# io-16x-fused-fm_beta.net
KiCad netlist of a schematic drawn in EAGLE
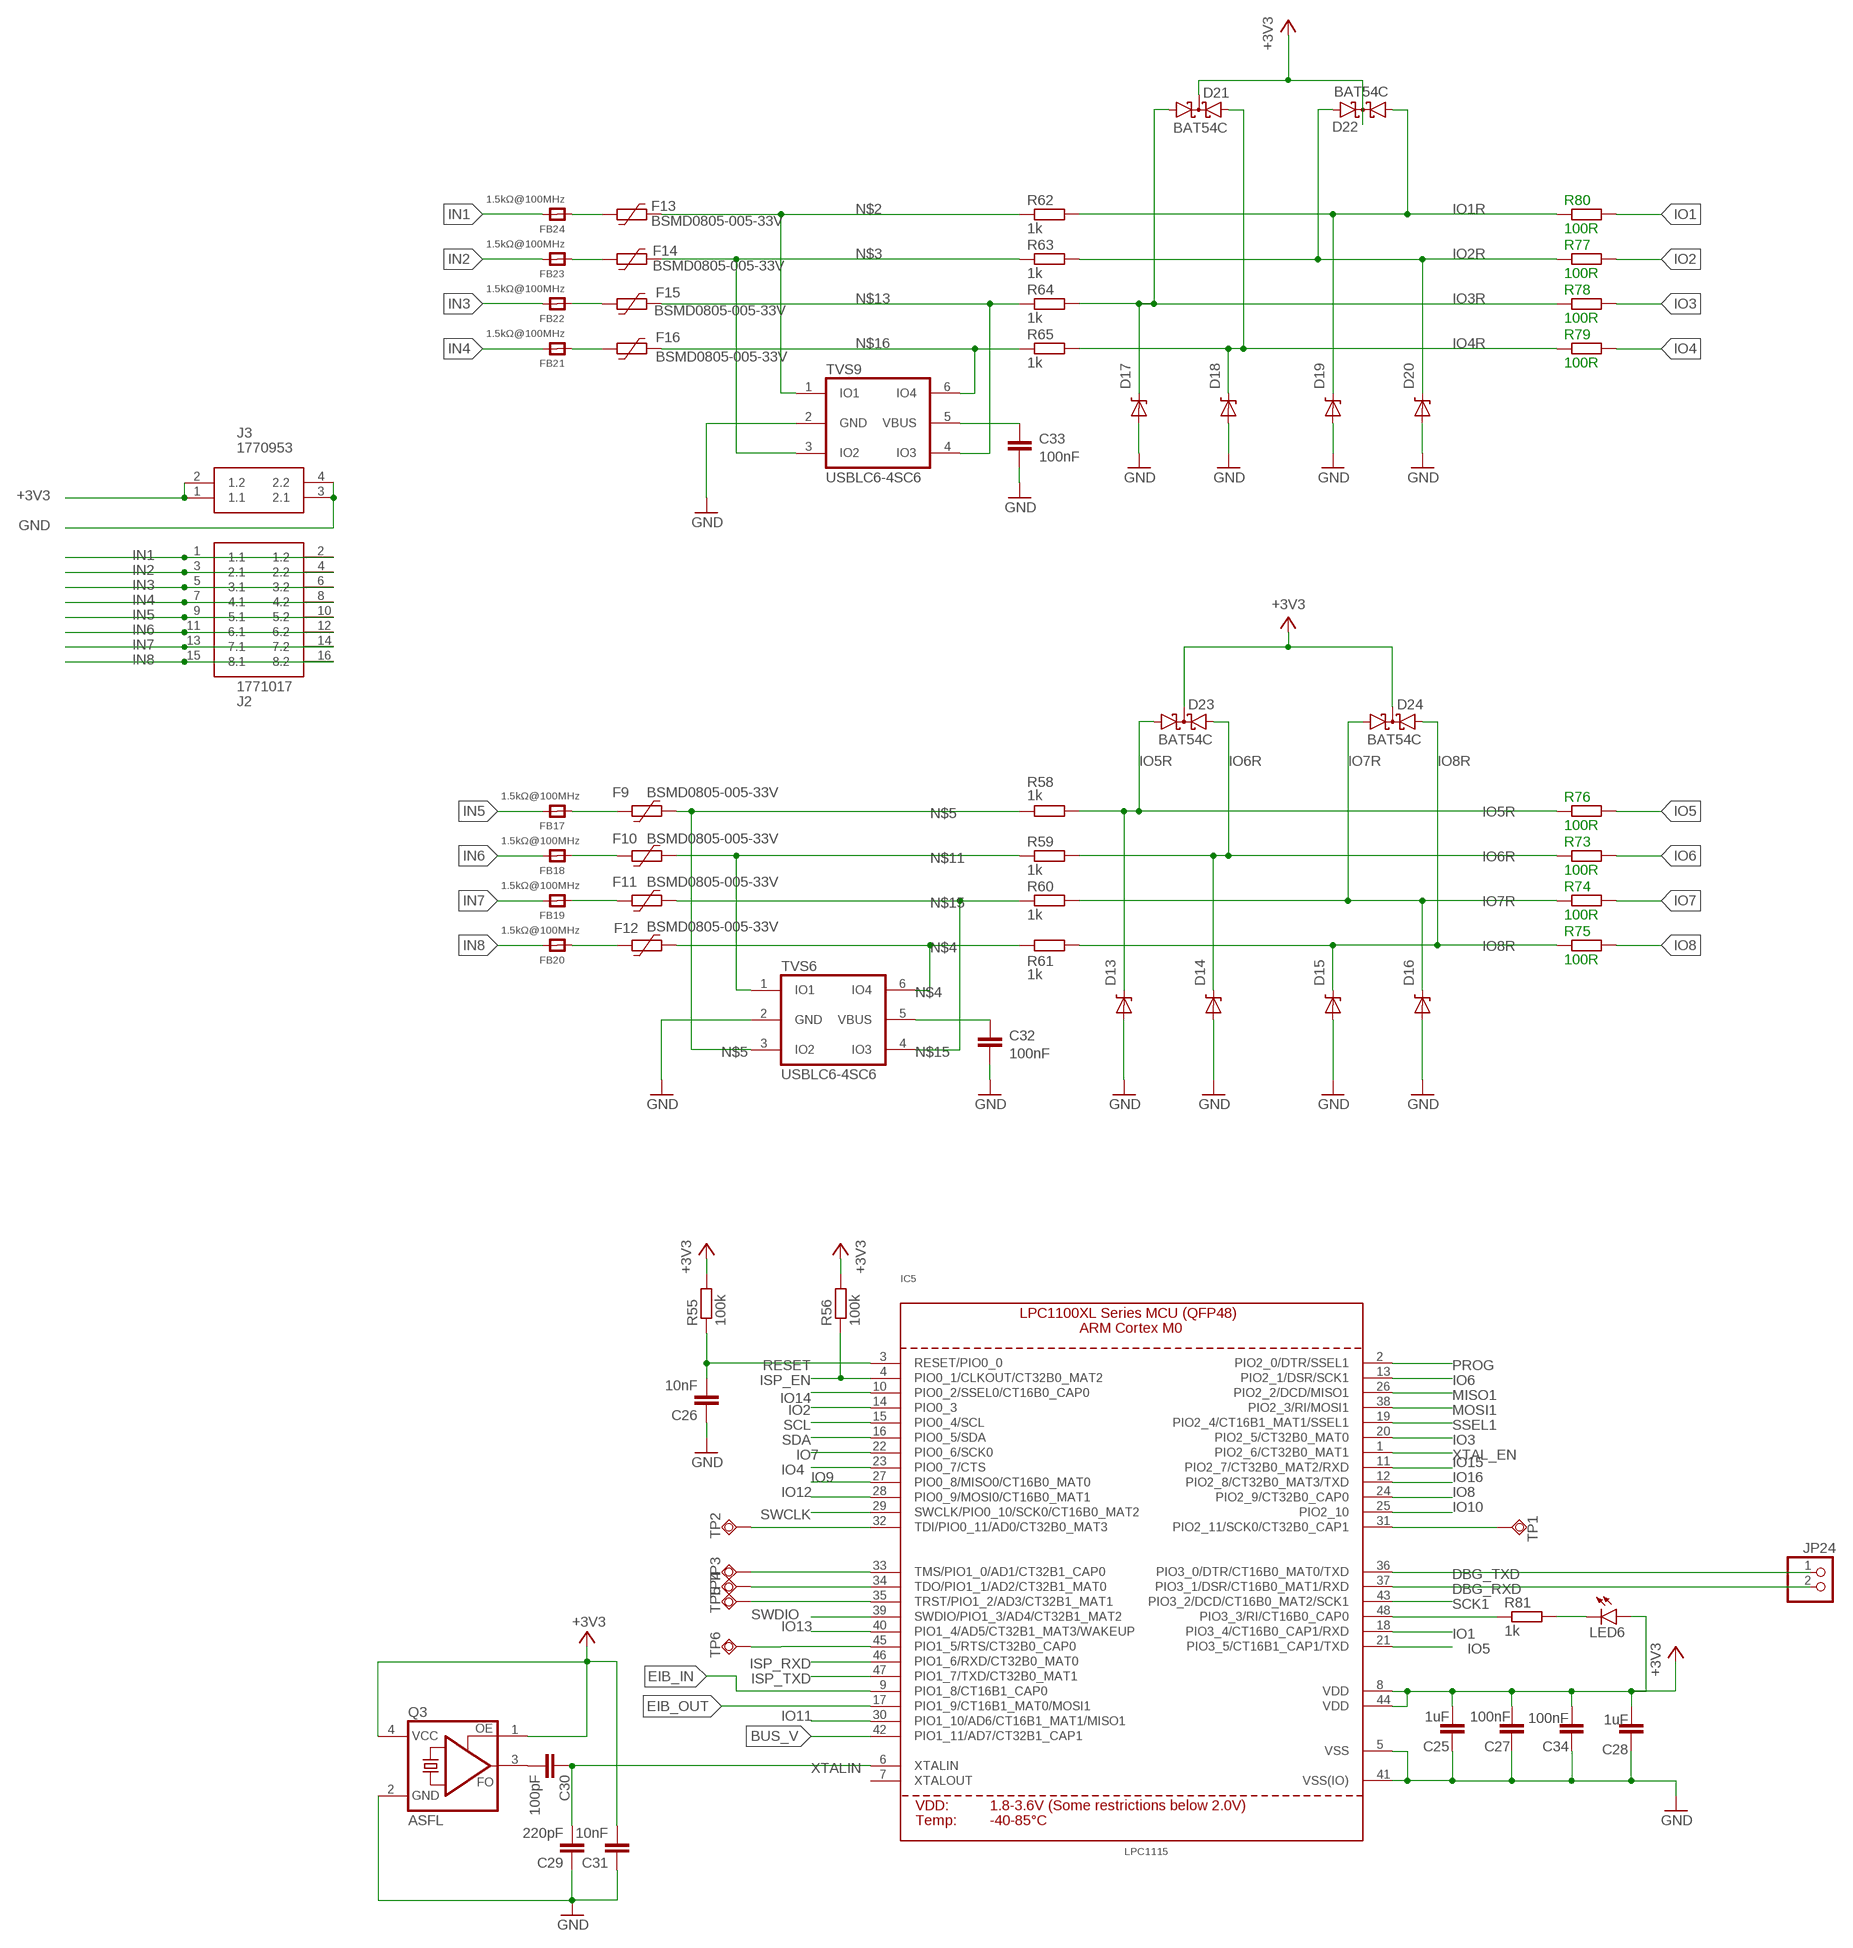
[diagram p0: schematic, sheet 1, part 1 of 2]
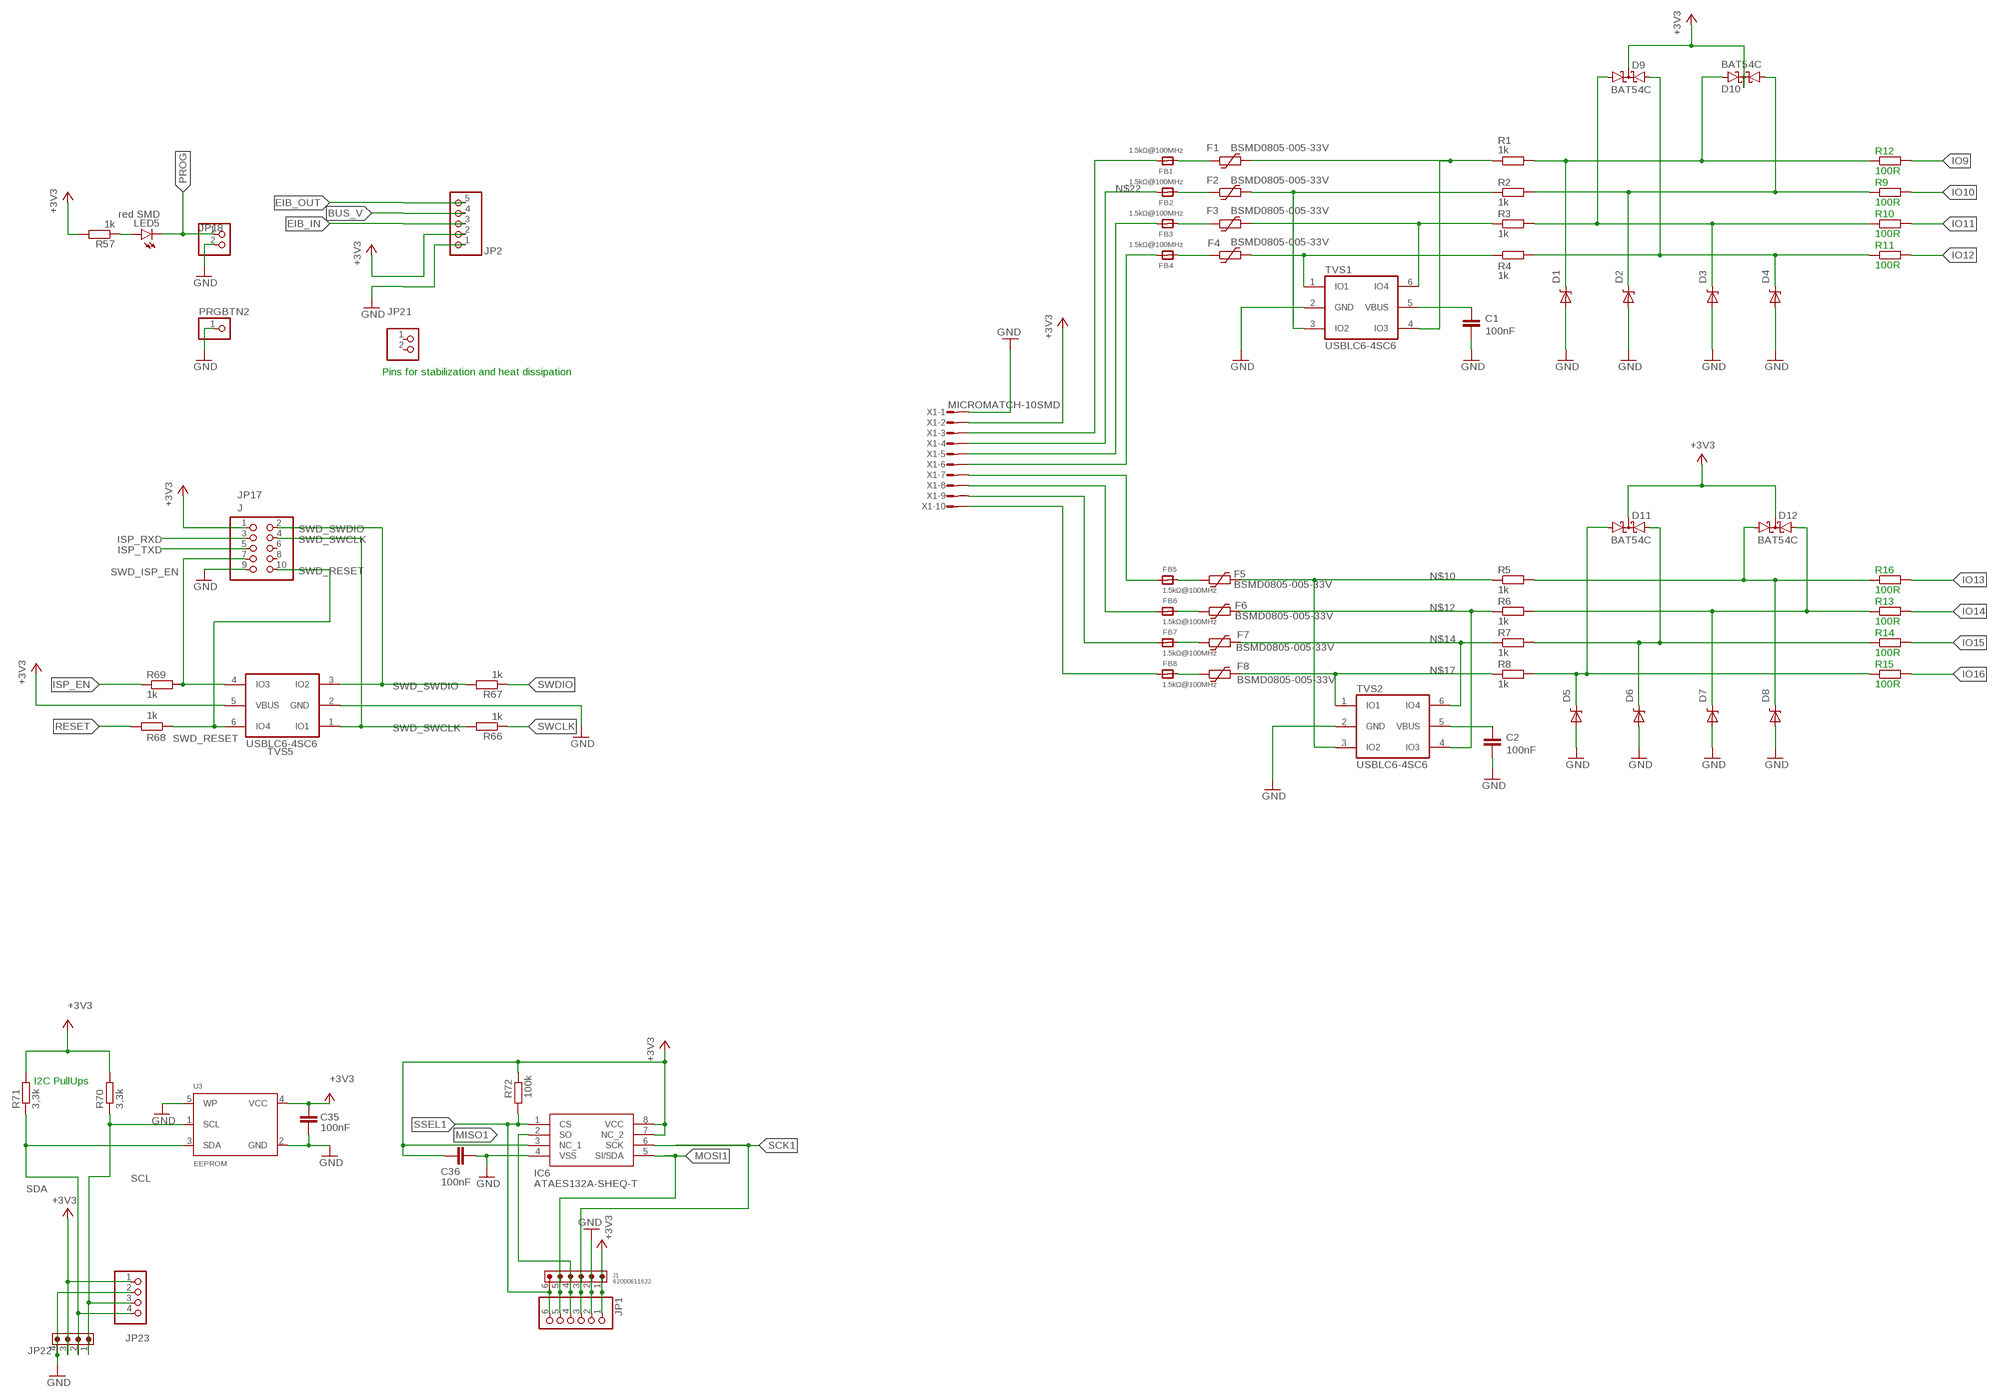
[diagram p1: schematic, sheet 1, part 2 of 2]

(export (version "E")
  (design (tool "Eeschema 10.0.6"))
  (components
    (comp (ref "C1")
      (value "100nF")
      (footprint "eagle-import:C0805")
      (libsource (lib "eagle-import") (part "C-EUC0805"))
    )
    (comp (ref "C2")
      (value "100nF")
      (footprint "eagle-import:C0805")
      (libsource (lib "eagle-import") (part "C-EUC0805"))
    )
    (comp (ref "C25")
      (value "1uF")
      (footprint "eagle-import:C0805")
      (libsource (lib "eagle-import") (part "C-EUC0805"))
    )
    (comp (ref "C26")
      (value "10nF")
      (footprint "eagle-import:C0805")
      (libsource (lib "eagle-import") (part "C-EUC0805"))
    )
    (comp (ref "C27")
      (value "100nF")
      (footprint "eagle-import:C0805")
      (libsource (lib "eagle-import") (part "C-EUC0805"))
    )
    (comp (ref "C28")
      (value "1uF")
      (footprint "eagle-import:C0805")
      (libsource (lib "eagle-import") (part "C-EUC0805"))
    )
    (comp (ref "C29")
      (value "220pF")
      (footprint "eagle-import:C0805")
      (libsource (lib "eagle-import") (part "C-EUC0805"))
    )
    (comp (ref "C30")
      (value "100pF")
      (footprint "eagle-import:C0805")
      (libsource (lib "eagle-import") (part "C-EUC0805"))
    )
    (comp (ref "C31")
      (value "10nF")
      (footprint "eagle-import:C0805")
      (libsource (lib "eagle-import") (part "C-EUC0805"))
    )
    (comp (ref "C32")
      (value "100nF")
      (footprint "eagle-import:C0805")
      (libsource (lib "eagle-import") (part "C-EUC0805"))
    )
    (comp (ref "C33")
      (value "100nF")
      (footprint "eagle-import:C0805")
      (libsource (lib "eagle-import") (part "C-EUC0805"))
    )
    (comp (ref "C34")
      (value "100nF")
      (footprint "eagle-import:C0805")
      (libsource (lib "eagle-import") (part "C-EUC0805"))
    )
    (comp (ref "C35")
      (value "100nF")
      (footprint "eagle-import:C0805")
      (libsource (lib "eagle-import") (part "C-EUC0805"))
    )
    (comp (ref "C36")
      (value "100nF")
      (footprint "eagle-import:C0805")
      (libsource (lib "eagle-import") (part "C-EUC0805"))
    )
    (comp (ref "D1")
      (value "DDZ9684")
      (footprint "eagle-import:SOD-123")
      (libsource (lib "eagle-import") (part "DIODE-ZENERSOD-123"))
    )
    (comp (ref "D2")
      (value "DDZ9684")
      (footprint "eagle-import:SOD-123")
      (libsource (lib "eagle-import") (part "DIODE-ZENERSOD-123"))
    )
    (comp (ref "D3")
      (value "DDZ9684")
      (footprint "eagle-import:SOD-123")
      (libsource (lib "eagle-import") (part "DIODE-ZENERSOD-123"))
    )
    (comp (ref "D4")
      (value "DDZ9684")
      (footprint "eagle-import:SOD-123")
      (libsource (lib "eagle-import") (part "DIODE-ZENERSOD-123"))
    )
    (comp (ref "D5")
      (value "DDZ9684")
      (footprint "eagle-import:SOD-123")
      (libsource (lib "eagle-import") (part "DIODE-ZENERSOD-123"))
    )
    (comp (ref "D6")
      (value "DDZ9684")
      (footprint "eagle-import:SOD-123")
      (libsource (lib "eagle-import") (part "DIODE-ZENERSOD-123"))
    )
    (comp (ref "D7")
      (value "DDZ9684")
      (footprint "eagle-import:SOD-123")
      (libsource (lib "eagle-import") (part "DIODE-ZENERSOD-123"))
    )
    (comp (ref "D8")
      (value "DDZ9684")
      (footprint "eagle-import:SOD-123")
      (libsource (lib "eagle-import") (part "DIODE-ZENERSOD-123"))
    )
    (comp (ref "D9")
      (value "BAT54C")
      (footprint "eagle-import:SOT23")
      (libsource (lib "eagle-import") (part "BAT54C"))
    )
    (comp (ref "D10")
      (value "BAT54C")
      (footprint "eagle-import:SOT23")
      (libsource (lib "eagle-import") (part "BAT54C"))
    )
    (comp (ref "D11")
      (value "BAT54C")
      (footprint "eagle-import:SOT23")
      (libsource (lib "eagle-import") (part "BAT54C"))
    )
    (comp (ref "D12")
      (value "BAT54C")
      (footprint "eagle-import:SOT23")
      (libsource (lib "eagle-import") (part "BAT54C"))
    )
    (comp (ref "D13")
      (value "DDZ9684")
      (footprint "eagle-import:SOD-123")
      (libsource (lib "eagle-import") (part "DIODE-ZENERSOD-123"))
    )
    (comp (ref "D14")
      (value "DDZ9684")
      (footprint "eagle-import:SOD-123")
      (libsource (lib "eagle-import") (part "DIODE-ZENERSOD-123"))
    )
    (comp (ref "D15")
      (value "DDZ9684")
      (footprint "eagle-import:SOD-123")
      (libsource (lib "eagle-import") (part "DIODE-ZENERSOD-123"))
    )
    (comp (ref "D16")
      (value "DDZ9684")
      (footprint "eagle-import:SOD-123")
      (libsource (lib "eagle-import") (part "DIODE-ZENERSOD-123"))
    )
    (comp (ref "D17")
      (value "DDZ9684")
      (footprint "eagle-import:SOD-123")
      (libsource (lib "eagle-import") (part "DIODE-ZENERSOD-123"))
    )
    (comp (ref "D18")
      (value "DDZ9684")
      (footprint "eagle-import:SOD-123")
      (libsource (lib "eagle-import") (part "DIODE-ZENERSOD-123"))
    )
    (comp (ref "D19")
      (value "DDZ9684")
      (footprint "eagle-import:SOD-123")
      (libsource (lib "eagle-import") (part "DIODE-ZENERSOD-123"))
    )
    (comp (ref "D20")
      (value "DDZ9684")
      (footprint "eagle-import:SOD-123")
      (libsource (lib "eagle-import") (part "DIODE-ZENERSOD-123"))
    )
    (comp (ref "D21")
      (value "BAT54C")
      (footprint "eagle-import:SOT23")
      (libsource (lib "eagle-import") (part "BAT54C"))
    )
    (comp (ref "D22")
      (value "BAT54C")
      (footprint "eagle-import:SOT23")
      (libsource (lib "eagle-import") (part "BAT54C"))
    )
    (comp (ref "D23")
      (value "BAT54C")
      (footprint "eagle-import:SOT23")
      (libsource (lib "eagle-import") (part "BAT54C"))
    )
    (comp (ref "D24")
      (value "BAT54C")
      (footprint "eagle-import:SOT23")
      (libsource (lib "eagle-import") (part "BAT54C"))
    )
    (comp (ref "F1")
      (value "BSMD0805-005-33V")
      (footprint "eagle-import:0805L")
      (fields (field (name "MF") "Littelfuse") (field (name "MPN") "0805L035"))
      (libsource (lib "eagle-import") (part "?0805L035"))
    )
    (comp (ref "F2")
      (value "BSMD0805-005-33V")
      (footprint "eagle-import:0805L")
      (fields (field (name "MF") "Littelfuse") (field (name "MPN") "0805L035"))
      (libsource (lib "eagle-import") (part "?0805L035"))
    )
    (comp (ref "F3")
      (value "BSMD0805-005-33V")
      (footprint "eagle-import:0805L")
      (fields (field (name "MF") "Littelfuse") (field (name "MPN") "0805L035"))
      (libsource (lib "eagle-import") (part "?0805L035"))
    )
    (comp (ref "F4")
      (value "BSMD0805-005-33V")
      (footprint "eagle-import:0805L")
      (fields (field (name "MF") "Littelfuse") (field (name "MPN") "0805L035"))
      (libsource (lib "eagle-import") (part "?0805L035"))
    )
    (comp (ref "F5")
      (value "BSMD0805-005-33V")
      (footprint "eagle-import:0805L")
      (fields (field (name "MF") "Littelfuse") (field (name "MPN") "0805L035"))
      (libsource (lib "eagle-import") (part "?0805L035"))
    )
    (comp (ref "F6")
      (value "BSMD0805-005-33V")
      (footprint "eagle-import:0805L")
      (fields (field (name "MF") "Littelfuse") (field (name "MPN") "0805L035"))
      (libsource (lib "eagle-import") (part "?0805L035"))
    )
    (comp (ref "F7")
      (value "BSMD0805-005-33V")
      (footprint "eagle-import:0805L")
      (fields (field (name "MF") "Littelfuse") (field (name "MPN") "0805L035"))
      (libsource (lib "eagle-import") (part "?0805L035"))
    )
    (comp (ref "F8")
      (value "BSMD0805-005-33V")
      (footprint "eagle-import:0805L")
      (fields (field (name "MF") "Littelfuse") (field (name "MPN") "0805L035"))
      (libsource (lib "eagle-import") (part "?0805L035"))
    )
    (comp (ref "F9")
      (value "BSMD0805-005-33V")
      (footprint "eagle-import:0805L")
      (fields (field (name "MF") "Littelfuse") (field (name "MPN") "0805L035"))
      (libsource (lib "eagle-import") (part "?0805L035"))
    )
    (comp (ref "F10")
      (value "BSMD0805-005-33V")
      (footprint "eagle-import:0805L")
      (fields (field (name "MF") "Littelfuse") (field (name "MPN") "0805L035"))
      (libsource (lib "eagle-import") (part "?0805L035"))
    )
    (comp (ref "F11")
      (value "BSMD0805-005-33V")
      (footprint "eagle-import:0805L")
      (fields (field (name "MF") "Littelfuse") (field (name "MPN") "0805L035"))
      (libsource (lib "eagle-import") (part "?0805L035"))
    )
    (comp (ref "F12")
      (value "BSMD0805-005-33V")
      (footprint "eagle-import:0805L")
      (fields (field (name "MF") "Littelfuse") (field (name "MPN") "0805L035"))
      (libsource (lib "eagle-import") (part "?0805L035"))
    )
    (comp (ref "F13")
      (value "BSMD0805-005-33V")
      (footprint "eagle-import:0805L")
      (fields (field (name "MF") "Littelfuse") (field (name "MPN") "0805L035"))
      (libsource (lib "eagle-import") (part "?0805L035"))
    )
    (comp (ref "F14")
      (value "BSMD0805-005-33V")
      (footprint "eagle-import:0805L")
      (fields (field (name "MF") "Littelfuse") (field (name "MPN") "0805L035"))
      (libsource (lib "eagle-import") (part "?0805L035"))
    )
    (comp (ref "F15")
      (value "BSMD0805-005-33V")
      (footprint "eagle-import:0805L")
      (fields (field (name "MF") "Littelfuse") (field (name "MPN") "0805L035"))
      (libsource (lib "eagle-import") (part "?0805L035"))
    )
    (comp (ref "F16")
      (value "BSMD0805-005-33V")
      (footprint "eagle-import:0805L")
      (fields (field (name "MF") "Littelfuse") (field (name "MPN") "0805L035"))
      (libsource (lib "eagle-import") (part "?0805L035"))
    )
    (comp (ref "FB1")
      (value "1.5kΩ@100MHz")
      (footprint "eagle-import:FERR_0805MP")
      (libsource (lib "eagle-import") (part "FERRITE2_0805MP"))
    )
    (comp (ref "FB2")
      (value "1.5kΩ@100MHz")
      (footprint "eagle-import:FERR_0805MP")
      (libsource (lib "eagle-import") (part "FERRITE2_0805MP"))
    )
    (comp (ref "FB3")
      (value "1.5kΩ@100MHz")
      (footprint "eagle-import:FERR_0805MP")
      (libsource (lib "eagle-import") (part "FERRITE2_0805MP"))
    )
    (comp (ref "FB4")
      (value "1.5kΩ@100MHz")
      (footprint "eagle-import:FERR_0805MP")
      (libsource (lib "eagle-import") (part "FERRITE2_0805MP"))
    )
    (comp (ref "FB5")
      (value "1.5kΩ@100MHz")
      (footprint "eagle-import:FERR_0805MP")
      (libsource (lib "eagle-import") (part "FERRITE2_0805MP"))
    )
    (comp (ref "FB6")
      (value "1.5kΩ@100MHz")
      (footprint "eagle-import:FERR_0805MP")
      (libsource (lib "eagle-import") (part "FERRITE2_0805MP"))
    )
    (comp (ref "FB7")
      (value "1.5kΩ@100MHz")
      (footprint "eagle-import:FERR_0805MP")
      (libsource (lib "eagle-import") (part "FERRITE2_0805MP"))
    )
    (comp (ref "FB8")
      (value "1.5kΩ@100MHz")
      (footprint "eagle-import:FERR_0805MP")
      (libsource (lib "eagle-import") (part "FERRITE2_0805MP"))
    )
    (comp (ref "FB17")
      (value "1.5kΩ@100MHz")
      (footprint "eagle-import:FERR_0805MP")
      (libsource (lib "eagle-import") (part "FERRITE2_0805MP"))
    )
    (comp (ref "FB18")
      (value "1.5kΩ@100MHz")
      (footprint "eagle-import:FERR_0805MP")
      (libsource (lib "eagle-import") (part "FERRITE2_0805MP"))
    )
    (comp (ref "FB19")
      (value "1.5kΩ@100MHz")
      (footprint "eagle-import:FERR_0805MP")
      (libsource (lib "eagle-import") (part "FERRITE2_0805MP"))
    )
    (comp (ref "FB20")
      (value "1.5kΩ@100MHz")
      (footprint "eagle-import:FERR_0805MP")
      (libsource (lib "eagle-import") (part "FERRITE2_0805MP"))
    )
    (comp (ref "FB21")
      (value "1.5kΩ@100MHz")
      (footprint "eagle-import:FERR_0805MP")
      (libsource (lib "eagle-import") (part "FERRITE2_0805MP"))
    )
    (comp (ref "FB22")
      (value "1.5kΩ@100MHz")
      (footprint "eagle-import:FERR_0805MP")
      (libsource (lib "eagle-import") (part "FERRITE2_0805MP"))
    )
    (comp (ref "FB23")
      (value "1.5kΩ@100MHz")
      (footprint "eagle-import:FERR_0805MP")
      (libsource (lib "eagle-import") (part "FERRITE2_0805MP"))
    )
    (comp (ref "FB24")
      (value "1.5kΩ@100MHz")
      (footprint "eagle-import:FERR_0805MP")
      (libsource (lib "eagle-import") (part "FERRITE2_0805MP"))
    )
    (comp (ref "IC5")
      (value "LPC1115")
      (footprint "eagle-import:LQFP48")
      (libsource (lib "eagle-import") (part "LPC1113/4/5_QFP48_XLSERIES"))
    )
    (comp (ref "IC6")
      (value "ATAES132A-SHEQ-T")
      (footprint "eagle-import:SOIC127P600X175-8N")
      (fields (field (name "MOUSER_PART_NUMBER") "556-ATAES132A-SHEQ-T"))
      (libsource (lib "eagle-import") (part "ATAES132A-SHEQ-T"))
    )
    (comp (ref "J1")
      (value "62000611622")
      (footprint "eagle-import:62000611622")
      (libsource (lib "eagle-import") (part "62000611622"))
    )
    (comp (ref "J2")
      (value "1771017")
      (footprint "eagle-import:1771017")
      (fields (field (name "MOUSER_PART_NUMBER") "651-1771017"))
      (libsource (lib "eagle-import") (part "1771017"))
    )
    (comp (ref "J3")
      (value "1770953")
      (footprint "eagle-import:1770953")
      (fields (field (name "MOUSER_PART_NUMBER") "651-1770953"))
      (libsource (lib "eagle-import") (part "1770953"))
    )
    (comp (ref "JP1")
      (value "PINHD-1X06_2.54-S")
      (footprint "eagle-import:1X06-S")
      (libsource (lib "eagle-import") (part "PINHD-1X06_2.54-S"))
    )
    (comp (ref "JP2")
      (value "PINHD-1X5")
      (footprint "eagle-import:1X05")
      (libsource (lib "eagle-import") (part "PINHD-1X5"))
    )
    (comp (ref "JP17")
      (value "J")
      (footprint "eagle-import:2X05M")
      (libsource (lib "eagle-import") (part "PINHD-2X05_2.00"))
    )
    (comp (ref "JP18")
      (value "PINHD-1X2")
      (footprint "eagle-import:1X02")
      (libsource (lib "eagle-import") (part "PINHD-1X2"))
    )
    (comp (ref "JP21")
      (value "PINHD-1X2")
      (footprint "eagle-import:1X02")
      (libsource (lib "eagle-import") (part "PINHD-1X2"))
    )
    (comp (ref "JP22")
      (value "62000411622")
      (footprint "eagle-import:62000411622")
      (libsource (lib "eagle-import") (part "62000411622"))
    )
    (comp (ref "JP23")
      (value "PINHD-1X4")
      (footprint "eagle-import:1X04")
      (libsource (lib "eagle-import") (part "PINHD-1X4"))
    )
    (comp (ref "JP24")
      (value "PINHD-1X2")
      (footprint "eagle-import:1X02")
      (libsource (lib "eagle-import") (part "PINHD-1X2"))
    )
    (comp (ref "LED5")
      (value "red SMD")
      (footprint "eagle-import:CHIPLED_0805")
      (libsource (lib "eagle-import") (part "LEDCHIPLED_0805"))
    )
    (comp (ref "LED6")
      (value "LEDCHIPLED_0805")
      (footprint "eagle-import:CHIPLED_0805")
      (libsource (lib "eagle-import") (part "LEDCHIPLED_0805"))
    )
    (comp (ref "PRGBTN2")
      (value "PINHD-1X1")
      (footprint "eagle-import:1X01")
      (libsource (lib "eagle-import") (part "PINHD-1X1"))
    )
    (comp (ref "Q3")
      (value "ASFL")
      (footprint "eagle-import:ASF")
      (fields (field (name "MPN") "ASFLM1-50.000MHZ-C-T"))
      (libsource (lib "eagle-import") (part "ASFL"))
    )
    (comp (ref "R1")
      (value "1k")
      (footprint "eagle-import:R0805")
      (libsource (lib "eagle-import") (part "R-EU_R0805"))
    )
    (comp (ref "R2")
      (value "1k")
      (footprint "eagle-import:R0805")
      (libsource (lib "eagle-import") (part "R-EU_R0805"))
    )
    (comp (ref "R3")
      (value "1k")
      (footprint "eagle-import:R0805")
      (libsource (lib "eagle-import") (part "R-EU_R0805"))
    )
    (comp (ref "R4")
      (value "1k")
      (footprint "eagle-import:R0805")
      (libsource (lib "eagle-import") (part "R-EU_R0805"))
    )
    (comp (ref "R5")
      (value "1k")
      (footprint "eagle-import:R0805")
      (libsource (lib "eagle-import") (part "R-EU_R0805"))
    )
    (comp (ref "R6")
      (value "1k")
      (footprint "eagle-import:R0805")
      (libsource (lib "eagle-import") (part "R-EU_R0805"))
    )
    (comp (ref "R7")
      (value "1k")
      (footprint "eagle-import:R0805")
      (libsource (lib "eagle-import") (part "R-EU_R0805"))
    )
    (comp (ref "R8")
      (value "1k")
      (footprint "eagle-import:R0805")
      (libsource (lib "eagle-import") (part "R-EU_R0805"))
    )
    (comp (ref "R9")
      (value "100R")
      (footprint "eagle-import:R0805")
      (libsource (lib "eagle-import") (part "R-EU_R0805"))
    )
    (comp (ref "R10")
      (value "100R")
      (footprint "eagle-import:R0805")
      (libsource (lib "eagle-import") (part "R-EU_R0805"))
    )
    (comp (ref "R11")
      (value "100R")
      (footprint "eagle-import:R0805")
      (libsource (lib "eagle-import") (part "R-EU_R0805"))
    )
    (comp (ref "R12")
      (value "100R")
      (footprint "eagle-import:R0805")
      (libsource (lib "eagle-import") (part "R-EU_R0805"))
    )
    (comp (ref "R13")
      (value "100R")
      (footprint "eagle-import:R0805")
      (libsource (lib "eagle-import") (part "R-EU_R0805"))
    )
    (comp (ref "R14")
      (value "100R")
      (footprint "eagle-import:R0805")
      (libsource (lib "eagle-import") (part "R-EU_R0805"))
    )
    (comp (ref "R15")
      (value "100R")
      (footprint "eagle-import:R0805")
      (libsource (lib "eagle-import") (part "R-EU_R0805"))
    )
    (comp (ref "R16")
      (value "100R")
      (footprint "eagle-import:R0805")
      (libsource (lib "eagle-import") (part "R-EU_R0805"))
    )
    (comp (ref "R55")
      (value "100k")
      (footprint "eagle-import:R0805")
      (libsource (lib "eagle-import") (part "R-EU_R0805"))
    )
    (comp (ref "R56")
      (value "100k")
      (footprint "eagle-import:R0805")
      (libsource (lib "eagle-import") (part "R-EU_R0805"))
    )
    (comp (ref "R57")
      (value "1k")
      (footprint "eagle-import:R0805")
      (libsource (lib "eagle-import") (part "R-EU_R0805"))
    )
    (comp (ref "R58")
      (value "1k")
      (footprint "eagle-import:R0805")
      (libsource (lib "eagle-import") (part "R-EU_R0805"))
    )
    (comp (ref "R59")
      (value "1k")
      (footprint "eagle-import:R0805")
      (libsource (lib "eagle-import") (part "R-EU_R0805"))
    )
    (comp (ref "R60")
      (value "1k")
      (footprint "eagle-import:R0805")
      (libsource (lib "eagle-import") (part "R-EU_R0805"))
    )
    (comp (ref "R61")
      (value "1k")
      (footprint "eagle-import:R0805")
      (libsource (lib "eagle-import") (part "R-EU_R0805"))
    )
    (comp (ref "R62")
      (value "1k")
      (footprint "eagle-import:R0805")
      (libsource (lib "eagle-import") (part "R-EU_R0805"))
    )
    (comp (ref "R63")
      (value "1k")
      (footprint "eagle-import:R0805")
      (libsource (lib "eagle-import") (part "R-EU_R0805"))
    )
    (comp (ref "R64")
      (value "1k")
      (footprint "eagle-import:R0805")
      (libsource (lib "eagle-import") (part "R-EU_R0805"))
    )
    (comp (ref "R65")
      (value "1k")
      (footprint "eagle-import:R0805")
      (libsource (lib "eagle-import") (part "R-EU_R0805"))
    )
    (comp (ref "R66")
      (value "1k")
      (footprint "eagle-import:R0805")
      (libsource (lib "eagle-import") (part "R-EU_R0805"))
    )
    (comp (ref "R67")
      (value "1k")
      (footprint "eagle-import:R0805")
      (libsource (lib "eagle-import") (part "R-EU_R0805"))
    )
    (comp (ref "R68")
      (value "1k")
      (footprint "eagle-import:R0805")
      (libsource (lib "eagle-import") (part "R-EU_R0805"))
    )
    (comp (ref "R69")
      (value "1k")
      (footprint "eagle-import:R0805")
      (libsource (lib "eagle-import") (part "R-EU_R0805"))
    )
    (comp (ref "R70")
      (value "3,3k")
      (footprint "eagle-import:R0805")
      (libsource (lib "eagle-import") (part "R-EU_R0805"))
    )
    (comp (ref "R71")
      (value "3,3k")
      (footprint "eagle-import:R0805")
      (libsource (lib "eagle-import") (part "R-EU_R0805"))
    )
    (comp (ref "R72")
      (value "100k")
      (footprint "eagle-import:R0805")
      (libsource (lib "eagle-import") (part "R-EU_R0805"))
    )
    (comp (ref "R73")
      (value "100R")
      (footprint "eagle-import:R0805")
      (libsource (lib "eagle-import") (part "R-EU_R0805"))
    )
    (comp (ref "R74")
      (value "100R")
      (footprint "eagle-import:R0805")
      (libsource (lib "eagle-import") (part "R-EU_R0805"))
    )
    (comp (ref "R75")
      (value "100R")
      (footprint "eagle-import:R0805")
      (libsource (lib "eagle-import") (part "R-EU_R0805"))
    )
    (comp (ref "R76")
      (value "100R")
      (footprint "eagle-import:R0805")
      (libsource (lib "eagle-import") (part "R-EU_R0805"))
    )
    (comp (ref "R77")
      (value "100R")
      (footprint "eagle-import:R0805")
      (libsource (lib "eagle-import") (part "R-EU_R0805"))
    )
    (comp (ref "R78")
      (value "100R")
      (footprint "eagle-import:R0805")
      (libsource (lib "eagle-import") (part "R-EU_R0805"))
    )
    (comp (ref "R79")
      (value "100R")
      (footprint "eagle-import:R0805")
      (libsource (lib "eagle-import") (part "R-EU_R0805"))
    )
    (comp (ref "R80")
      (value "100R")
      (footprint "eagle-import:R0805")
      (libsource (lib "eagle-import") (part "R-EU_R0805"))
    )
    (comp (ref "R81")
      (value "1k")
      (footprint "eagle-import:R0805")
      (libsource (lib "eagle-import") (part "R-EU_R0805"))
    )
    (comp (ref "TP1")
      (value "TPSQTP08R")
      (footprint "eagle-import:TP08R")
      (libsource (lib "eagle-import") (part "TPSQTP08R"))
    )
    (comp (ref "TP2")
      (value "TPSQTP08R")
      (footprint "eagle-import:TP08R")
      (libsource (lib "eagle-import") (part "TPSQTP08R"))
    )
    (comp (ref "TP3")
      (value "TPSQTP08R")
      (footprint "eagle-import:TP08R")
      (libsource (lib "eagle-import") (part "TPSQTP08R"))
    )
    (comp (ref "TP4")
      (value "TPSQTP08R")
      (footprint "eagle-import:TP08R")
      (libsource (lib "eagle-import") (part "TPSQTP08R"))
    )
    (comp (ref "TP5")
      (value "TPSQTP08R")
      (footprint "eagle-import:TP08R")
      (libsource (lib "eagle-import") (part "TPSQTP08R"))
    )
    (comp (ref "TP6")
      (value "TPSQTP08R")
      (footprint "eagle-import:TP08R")
      (libsource (lib "eagle-import") (part "TPSQTP08R"))
    )
    (comp (ref "TVS1")
      (value "USBLC6-4SC6")
      (footprint "eagle-import:SOT-23-6L")
      (libsource (lib "eagle-import") (part "USBLC6-4SC6"))
    )
    (comp (ref "TVS2")
      (value "USBLC6-4SC6")
      (footprint "eagle-import:SOT-23-6L")
      (libsource (lib "eagle-import") (part "USBLC6-4SC6"))
    )
    (comp (ref "TVS5")
      (value "USBLC6-4SC6")
      (footprint "eagle-import:SOT-23-6L")
      (libsource (lib "eagle-import") (part "USBLC6-4SC6"))
    )
    (comp (ref "TVS6")
      (value "USBLC6-4SC6")
      (footprint "eagle-import:SOT-23-6L")
      (libsource (lib "eagle-import") (part "USBLC6-4SC6"))
    )
    (comp (ref "TVS9")
      (value "USBLC6-4SC6")
      (footprint "eagle-import:SOT-23-6L")
      (libsource (lib "eagle-import") (part "USBLC6-4SC6"))
    )
    (comp (ref "U3")
      (value "EEPROM")
      (footprint "eagle-import:SOT23-5")
      (libsource (lib "eagle-import") (part "EEPROM_I2C_MCP24AA32"))
    )
    (comp (ref "X1")
      (value "MICROMATCH-10SMD")
      (footprint "eagle-import:MICROMATCH-10SMD")
      (libsource (lib "eagle-import") (part "MICROMATCH-10SMD"))
    )
  )
  (nets
    (net (code "1") (name "+3V3") (class "Default")
      (node (ref "C25") (pin "2") (pinfunction "2_2") (pintype "passive"))
      (node (ref "C27") (pin "2") (pinfunction "2_2") (pintype "passive"))
      (node (ref "C28") (pin "2") (pinfunction "2_2") (pintype "passive"))
      (node (ref "C31") (pin "2") (pinfunction "2_2") (pintype "passive"))
      (node (ref "C34") (pin "2") (pinfunction "2_2") (pintype "passive"))
      (node (ref "C35") (pin "1") (pinfunction "1_1") (pintype "passive"))
      (node (ref "C36") (pin "1") (pinfunction "1_1") (pintype "passive"))
      (node (ref "D10") (pin "3") (pinfunction "CC_3") (pintype "passive"))
      (node (ref "D11") (pin "3") (pinfunction "CC_3") (pintype "passive"))
      (node (ref "D12") (pin "3") (pinfunction "CC_3") (pintype "passive"))
      (node (ref "D21") (pin "3") (pinfunction "CC_3") (pintype "passive"))
      (node (ref "D22") (pin "3") (pinfunction "CC_3") (pintype "passive"))
      (node (ref "D23") (pin "3") (pinfunction "CC_3") (pintype "passive"))
      (node (ref "D24") (pin "3") (pinfunction "CC_3") (pintype "passive"))
      (node (ref "D9") (pin "3") (pinfunction "CC_3") (pintype "passive"))
      (node (ref "IC5") (pin "44") (pinfunction "VDD_44") (pintype "power_in"))
      (node (ref "IC5") (pin "8") (pinfunction "VDD_8") (pintype "power_in"))
      (node (ref "IC6") (pin "3") (pinfunction "NC_1_3") (pintype "bidirectional"))
      (node (ref "IC6") (pin "7") (pinfunction "NC_2_7") (pintype "bidirectional"))
      (node (ref "IC6") (pin "8") (pinfunction "VCC_8") (pintype "bidirectional"))
      (node (ref "J1") (pin "1") (pinfunction "1_1") (pintype "passive"))
      (node (ref "J3") (pin "1") (pinfunction "1.1_1") (pintype "bidirectional"))
      (node (ref "J3") (pin "2") (pinfunction "1.2_2") (pintype "bidirectional"))
      (node (ref "JP1") (pin "1") (pinfunction "1_1") (pintype "passive"))
      (node (ref "JP17") (pin "1") (pinfunction "1_1") (pintype "passive"))
      (node (ref "JP2") (pin "2") (pinfunction "2_2") (pintype "passive"))
      (node (ref "JP22") (pin "3") (pinfunction "3_3") (pintype "passive"))
      (node (ref "JP23") (pin "1") (pinfunction "1_1") (pintype "passive"))
      (node (ref "LED6") (pin "A") (pinfunction "A_A") (pintype "passive"))
      (node (ref "Q3") (pin "1") (pinfunction "OE_1") (pintype "input"))
      (node (ref "Q3") (pin "4") (pinfunction "VCC_4") (pintype "power_in"))
      (node (ref "R55") (pin "2") (pinfunction "2_2") (pintype "passive"))
      (node (ref "R56") (pin "2") (pinfunction "2_2") (pintype "passive"))
      (node (ref "R57") (pin "2") (pinfunction "2_2") (pintype "passive"))
      (node (ref "R70") (pin "2") (pinfunction "2_2") (pintype "passive"))
      (node (ref "R71") (pin "2") (pinfunction "2_2") (pintype "passive"))
      (node (ref "R72") (pin "2") (pinfunction "2_2") (pintype "passive"))
      (node (ref "TVS5") (pin "5") (pinfunction "VBUS_5") (pintype "bidirectional"))
      (node (ref "U3") (pin "4") (pinfunction "VCC_4") (pintype "bidirectional"))
      (node (ref "X1") (pin "2") (pinfunction "S_2") (pintype "passive"))
    )
    (net (code "2") (name "/DBG_RXD") (class "Default")
      (node (ref "IC5") (pin "37") (pinfunction "PIO3_1/DSR/CT16B0_MAT1/RXD_37") (pintype "bidirectional"))
      (node (ref "JP24") (pin "2") (pinfunction "2_2") (pintype "passive"))
    )
    (net (code "3") (name "/DBG_TXD") (class "Default")
      (node (ref "IC5") (pin "36") (pinfunction "PIO3_0/DTR/CT16B0_MAT0/TXD_36") (pintype "bidirectional"))
      (node (ref "JP24") (pin "1") (pinfunction "1_1") (pintype "passive"))
    )
    (net (code "4") (name "/IO1R") (class "Default")
      (node (ref "D19") (pin "C") (pinfunction "C_C") (pintype "passive"))
      (node (ref "D22") (pin "1") (pinfunction "A1_1") (pintype "passive"))
      (node (ref "R62") (pin "2") (pinfunction "2_2") (pintype "passive"))
      (node (ref "R80") (pin "1") (pinfunction "1_1") (pintype "passive"))
    )
    (net (code "5") (name "/IO2R") (class "Default")
      (node (ref "D20") (pin "C") (pinfunction "C_C") (pintype "passive"))
      (node (ref "D22") (pin "2") (pinfunction "A2_2") (pintype "passive"))
      (node (ref "R63") (pin "2") (pinfunction "2_2") (pintype "passive"))
      (node (ref "R77") (pin "1") (pinfunction "1_1") (pintype "passive"))
    )
    (net (code "6") (name "/IO3R") (class "Default")
      (node (ref "D17") (pin "C") (pinfunction "C_C") (pintype "passive"))
      (node (ref "D21") (pin "1") (pinfunction "A1_1") (pintype "passive"))
      (node (ref "R64") (pin "2") (pinfunction "2_2") (pintype "passive"))
      (node (ref "R78") (pin "1") (pinfunction "1_1") (pintype "passive"))
    )
    (net (code "7") (name "/IO4R") (class "Default")
      (node (ref "D18") (pin "C") (pinfunction "C_C") (pintype "passive"))
      (node (ref "D21") (pin "2") (pinfunction "A2_2") (pintype "passive"))
      (node (ref "R65") (pin "2") (pinfunction "2_2") (pintype "passive"))
      (node (ref "R79") (pin "1") (pinfunction "1_1") (pintype "passive"))
    )
    (net (code "8") (name "/IO5R") (class "Default")
      (node (ref "D13") (pin "C") (pinfunction "C_C") (pintype "passive"))
      (node (ref "D23") (pin "1") (pinfunction "A1_1") (pintype "passive"))
      (node (ref "R58") (pin "2") (pinfunction "2_2") (pintype "passive"))
      (node (ref "R76") (pin "1") (pinfunction "1_1") (pintype "passive"))
    )
    (net (code "9") (name "/IO6R") (class "Default")
      (node (ref "D14") (pin "C") (pinfunction "C_C") (pintype "passive"))
      (node (ref "D23") (pin "2") (pinfunction "A2_2") (pintype "passive"))
      (node (ref "R59") (pin "2") (pinfunction "2_2") (pintype "passive"))
      (node (ref "R73") (pin "1") (pinfunction "1_1") (pintype "passive"))
    )
    (net (code "10") (name "/IO7R") (class "Default")
      (node (ref "D16") (pin "C") (pinfunction "C_C") (pintype "passive"))
      (node (ref "D24") (pin "1") (pinfunction "A1_1") (pintype "passive"))
      (node (ref "R60") (pin "2") (pinfunction "2_2") (pintype "passive"))
      (node (ref "R74") (pin "1") (pinfunction "1_1") (pintype "passive"))
    )
    (net (code "11") (name "/IO8R") (class "Default")
      (node (ref "D15") (pin "C") (pinfunction "C_C") (pintype "passive"))
      (node (ref "D24") (pin "2") (pinfunction "A2_2") (pintype "passive"))
      (node (ref "R61") (pin "2") (pinfunction "2_2") (pintype "passive"))
      (node (ref "R75") (pin "1") (pinfunction "1_1") (pintype "passive"))
    )
    (net (code "12") (name "/ISP_RXD") (class "Default")
      (node (ref "IC5") (pin "46") (pinfunction "PIO1_6/RXD/CT32B0_MAT0_46") (pintype "bidirectional"))
      (node (ref "JP17") (pin "3") (pinfunction "3_3") (pintype "passive"))
    )
    (net (code "13") (name "/ISP_TXD") (class "Default")
      (node (ref "IC5") (pin "47") (pinfunction "PIO1_7/TXD/CT32B0_MAT1_47") (pintype "bidirectional"))
      (node (ref "JP17") (pin "5") (pinfunction "5_5") (pintype "passive"))
    )
    (net (code "14") (name "/N$2") (class "Default")
      (node (ref "F13") (pin "2") (pinfunction "2_2") (pintype "passive"))
      (node (ref "R62") (pin "1") (pinfunction "1_1") (pintype "passive"))
      (node (ref "TVS9") (pin "1") (pinfunction "IO1_1") (pintype "bidirectional"))
    )
    (net (code "15") (name "/N$3") (class "Default")
      (node (ref "F14") (pin "2") (pinfunction "2_2") (pintype "passive"))
      (node (ref "R63") (pin "1") (pinfunction "1_1") (pintype "passive"))
      (node (ref "TVS9") (pin "3") (pinfunction "IO2_3") (pintype "bidirectional"))
    )
    (net (code "16") (name "/N$4") (class "Default")
      (node (ref "F12") (pin "2") (pinfunction "2_2") (pintype "passive"))
      (node (ref "R61") (pin "1") (pinfunction "1_1") (pintype "passive"))
      (node (ref "TVS6") (pin "6") (pinfunction "IO4_6") (pintype "bidirectional"))
    )
    (net (code "17") (name "/N$5") (class "Default")
      (node (ref "F9") (pin "2") (pinfunction "2_2") (pintype "passive"))
      (node (ref "R58") (pin "1") (pinfunction "1_1") (pintype "passive"))
      (node (ref "TVS6") (pin "3") (pinfunction "IO2_3") (pintype "bidirectional"))
    )
    (net (code "18") (name "/N$10") (class "Default")
      (node (ref "F5") (pin "2") (pinfunction "2_2") (pintype "passive"))
      (node (ref "R5") (pin "1") (pinfunction "1_1") (pintype "passive"))
      (node (ref "TVS2") (pin "3") (pinfunction "IO2_3") (pintype "bidirectional"))
    )
    (net (code "19") (name "/N$11") (class "Default")
      (node (ref "F10") (pin "2") (pinfunction "2_2") (pintype "passive"))
      (node (ref "R59") (pin "1") (pinfunction "1_1") (pintype "passive"))
      (node (ref "TVS6") (pin "1") (pinfunction "IO1_1") (pintype "bidirectional"))
    )
    (net (code "20") (name "/N$12") (class "Default")
      (node (ref "F6") (pin "2") (pinfunction "2_2") (pintype "passive"))
      (node (ref "R6") (pin "1") (pinfunction "1_1") (pintype "passive"))
      (node (ref "TVS2") (pin "4") (pinfunction "IO3_4") (pintype "bidirectional"))
    )
    (net (code "21") (name "/N$13") (class "Default")
      (node (ref "F15") (pin "2") (pinfunction "2_2") (pintype "passive"))
      (node (ref "R64") (pin "1") (pinfunction "1_1") (pintype "passive"))
      (node (ref "TVS9") (pin "4") (pinfunction "IO3_4") (pintype "bidirectional"))
    )
    (net (code "22") (name "/N$14") (class "Default")
      (node (ref "F7") (pin "2") (pinfunction "2_2") (pintype "passive"))
      (node (ref "R7") (pin "1") (pinfunction "1_1") (pintype "passive"))
      (node (ref "TVS2") (pin "6") (pinfunction "IO4_6") (pintype "bidirectional"))
    )
    (net (code "23") (name "/N$15") (class "Default")
      (node (ref "F11") (pin "2") (pinfunction "2_2") (pintype "passive"))
      (node (ref "R60") (pin "1") (pinfunction "1_1") (pintype "passive"))
      (node (ref "TVS6") (pin "4") (pinfunction "IO3_4") (pintype "bidirectional"))
    )
    (net (code "24") (name "/N$16") (class "Default")
      (node (ref "F16") (pin "2") (pinfunction "2_2") (pintype "passive"))
      (node (ref "R65") (pin "1") (pinfunction "1_1") (pintype "passive"))
      (node (ref "TVS9") (pin "6") (pinfunction "IO4_6") (pintype "bidirectional"))
    )
    (net (code "25") (name "/N$17") (class "Default")
      (node (ref "F8") (pin "2") (pinfunction "2_2") (pintype "passive"))
      (node (ref "R8") (pin "1") (pinfunction "1_1") (pintype "passive"))
      (node (ref "TVS2") (pin "1") (pinfunction "IO1_1") (pintype "bidirectional"))
    )
    (net (code "26") (name "/N$22") (class "Default")
      (node (ref "FB2") (pin "2") (pinfunction "P$2_2") (pintype "passive"))
      (node (ref "X1") (pin "4") (pinfunction "S_4") (pintype "passive"))
    )
    (net (code "27") (name "/SCL") (class "Default")
      (node (ref "IC5") (pin "15") (pinfunction "PIO0_4/SCL_15") (pintype "bidirectional"))
      (node (ref "JP22") (pin "1") (pinfunction "1_1") (pintype "passive"))
      (node (ref "JP23") (pin "3") (pinfunction "3_3") (pintype "passive"))
      (node (ref "R70") (pin "1") (pinfunction "1_1") (pintype "passive"))
      (node (ref "U3") (pin "1") (pinfunction "SCL_1") (pintype "bidirectional"))
    )
    (net (code "28") (name "/SDA") (class "Default")
      (node (ref "IC5") (pin "16") (pinfunction "PIO0_5/SDA_16") (pintype "bidirectional"))
      (node (ref "JP22") (pin "2") (pinfunction "2_2") (pintype "passive"))
      (node (ref "JP23") (pin "4") (pinfunction "4_4") (pintype "passive"))
      (node (ref "R71") (pin "1") (pinfunction "1_1") (pintype "passive"))
      (node (ref "U3") (pin "3") (pinfunction "SDA_3") (pintype "bidirectional"))
    )
    (net (code "29") (name "/SWD_ISP_EN") (class "Default")
      (node (ref "JP17") (pin "7") (pinfunction "7_7") (pintype "passive"))
      (node (ref "R69") (pin "2") (pinfunction "2_2") (pintype "passive"))
      (node (ref "TVS5") (pin "4") (pinfunction "IO3_4") (pintype "bidirectional"))
    )
    (net (code "30") (name "/SWD_RESET") (class "Default")
      (node (ref "JP17") (pin "10") (pinfunction "10_10") (pintype "passive"))
      (node (ref "R68") (pin "1") (pinfunction "1_1") (pintype "passive"))
      (node (ref "TVS5") (pin "6") (pinfunction "IO4_6") (pintype "bidirectional"))
    )
    (net (code "31") (name "/SWD_SWCLK") (class "Default")
      (node (ref "JP17") (pin "4") (pinfunction "4_4") (pintype "passive"))
      (node (ref "R66") (pin "2") (pinfunction "2_2") (pintype "passive"))
      (node (ref "TVS5") (pin "1") (pinfunction "IO1_1") (pintype "bidirectional"))
    )
    (net (code "32") (name "/SWD_SWDIO") (class "Default")
      (node (ref "JP17") (pin "2") (pinfunction "2_2") (pintype "passive"))
      (node (ref "R67") (pin "2") (pinfunction "2_2") (pintype "passive"))
      (node (ref "TVS5") (pin "3") (pinfunction "IO2_3") (pintype "bidirectional"))
    )
    (net (code "33") (name "/XTALIN") (class "Default")
      (node (ref "C29") (pin "2") (pinfunction "2_2") (pintype "passive"))
      (node (ref "C30") (pin "1") (pinfunction "1_1") (pintype "passive"))
      (node (ref "IC5") (pin "6") (pinfunction "XTALIN_6") (pintype "input"))
    )
    (net (code "34") (name "/XTAL_EN") (class "Default")
      (node (ref "IC5") (pin "1") (pinfunction "PIO2_6/CT32B0_MAT1_1") (pintype "bidirectional"))
    )
    (net (code "35") (name "BUS_V") (class "Default")
      (node (ref "IC5") (pin "42") (pinfunction "PIO1_11/AD7/CT32B1_CAP1_42") (pintype "bidirectional"))
      (node (ref "JP2") (pin "4") (pinfunction "4_4") (pintype "passive"))
    )
    (net (code "36") (name "EIB_IN") (class "Default")
      (node (ref "IC5") (pin "9") (pinfunction "PIO1_8/CT16B1_CAP0_9") (pintype "bidirectional"))
      (node (ref "JP2") (pin "3") (pinfunction "3_3") (pintype "passive"))
    )
    (net (code "37") (name "EIB_OUT") (class "Default")
      (node (ref "IC5") (pin "17") (pinfunction "PIO1_9/CT16B1_MAT0/MOSI1_17") (pintype "bidirectional"))
      (node (ref "JP2") (pin "5") (pinfunction "5_5") (pintype "passive"))
    )
    (net (code "38") (name "GND") (class "Default")
      (node (ref "C1") (pin "1") (pinfunction "1_1") (pintype "passive"))
      (node (ref "C2") (pin "1") (pinfunction "1_1") (pintype "passive"))
      (node (ref "C25") (pin "1") (pinfunction "1_1") (pintype "passive"))
      (node (ref "C26") (pin "1") (pinfunction "1_1") (pintype "passive"))
      (node (ref "C27") (pin "1") (pinfunction "1_1") (pintype "passive"))
      (node (ref "C28") (pin "1") (pinfunction "1_1") (pintype "passive"))
      (node (ref "C29") (pin "1") (pinfunction "1_1") (pintype "passive"))
      (node (ref "C31") (pin "1") (pinfunction "1_1") (pintype "passive"))
      (node (ref "C32") (pin "1") (pinfunction "1_1") (pintype "passive"))
      (node (ref "C33") (pin "1") (pinfunction "1_1") (pintype "passive"))
      (node (ref "C34") (pin "1") (pinfunction "1_1") (pintype "passive"))
      (node (ref "C35") (pin "2") (pinfunction "2_2") (pintype "passive"))
      (node (ref "C36") (pin "2") (pinfunction "2_2") (pintype "passive"))
      (node (ref "D1") (pin "A") (pinfunction "A_A") (pintype "passive"))
      (node (ref "D13") (pin "A") (pinfunction "A_A") (pintype "passive"))
      (node (ref "D14") (pin "A") (pinfunction "A_A") (pintype "passive"))
      (node (ref "D15") (pin "A") (pinfunction "A_A") (pintype "passive"))
      (node (ref "D16") (pin "A") (pinfunction "A_A") (pintype "passive"))
      (node (ref "D17") (pin "A") (pinfunction "A_A") (pintype "passive"))
      (node (ref "D18") (pin "A") (pinfunction "A_A") (pintype "passive"))
      (node (ref "D19") (pin "A") (pinfunction "A_A") (pintype "passive"))
      (node (ref "D2") (pin "A") (pinfunction "A_A") (pintype "passive"))
      (node (ref "D20") (pin "A") (pinfunction "A_A") (pintype "passive"))
      (node (ref "D3") (pin "A") (pinfunction "A_A") (pintype "passive"))
      (node (ref "D4") (pin "A") (pinfunction "A_A") (pintype "passive"))
      (node (ref "D5") (pin "A") (pinfunction "A_A") (pintype "passive"))
      (node (ref "D6") (pin "A") (pinfunction "A_A") (pintype "passive"))
      (node (ref "D7") (pin "A") (pinfunction "A_A") (pintype "passive"))
      (node (ref "D8") (pin "A") (pinfunction "A_A") (pintype "passive"))
      (node (ref "IC5") (pin "41") (pinfunction "VSS(IO)_41") (pintype "power_in"))
      (node (ref "IC5") (pin "5") (pinfunction "VSS_5") (pintype "power_in"))
      (node (ref "IC6") (pin "4") (pinfunction "VSS_4") (pintype "bidirectional"))
      (node (ref "J1") (pin "2") (pinfunction "2_2") (pintype "passive"))
      (node (ref "J3") (pin "3") (pinfunction "2.1_3") (pintype "bidirectional"))
      (node (ref "J3") (pin "4") (pinfunction "2.2_4") (pintype "bidirectional"))
      (node (ref "JP1") (pin "2") (pinfunction "2_2") (pintype "passive"))
      (node (ref "JP17") (pin "9") (pinfunction "9_9") (pintype "passive"))
      (node (ref "JP18") (pin "2") (pinfunction "2_2") (pintype "passive"))
      (node (ref "JP2") (pin "1") (pinfunction "1_1") (pintype "passive"))
      (node (ref "JP22") (pin "4") (pinfunction "4_4") (pintype "passive"))
      (node (ref "JP23") (pin "2") (pinfunction "2_2") (pintype "passive"))
      (node (ref "PRGBTN2") (pin "1") (pinfunction "1_1") (pintype "passive"))
      (node (ref "Q3") (pin "2") (pinfunction "GND_2") (pintype "power_in"))
      (node (ref "TVS1") (pin "2") (pinfunction "GND_2") (pintype "bidirectional"))
      (node (ref "TVS2") (pin "2") (pinfunction "GND_2") (pintype "bidirectional"))
      (node (ref "TVS5") (pin "2") (pinfunction "GND_2") (pintype "bidirectional"))
      (node (ref "TVS6") (pin "2") (pinfunction "GND_2") (pintype "bidirectional"))
      (node (ref "TVS9") (pin "2") (pinfunction "GND_2") (pintype "bidirectional"))
      (node (ref "U3") (pin "2") (pinfunction "GND_2") (pintype "bidirectional"))
      (node (ref "U3") (pin "5") (pinfunction "WP_5") (pintype "bidirectional"))
      (node (ref "X1") (pin "1") (pinfunction "S_1") (pintype "passive"))
    )
    (net (code "39") (name "IN1") (class "Default")
      (node (ref "FB24") (pin "2") (pinfunction "P$2_2") (pintype "passive"))
      (node (ref "J2") (pin "1") (pinfunction "1.1_1") (pintype "bidirectional"))
      (node (ref "J2") (pin "2") (pinfunction "1.2_2") (pintype "bidirectional"))
    )
    (net (code "40") (name "IN2") (class "Default")
      (node (ref "FB23") (pin "2") (pinfunction "P$2_2") (pintype "passive"))
      (node (ref "J2") (pin "3") (pinfunction "2.1_3") (pintype "bidirectional"))
      (node (ref "J2") (pin "4") (pinfunction "2.2_4") (pintype "bidirectional"))
    )
    (net (code "41") (name "IN3") (class "Default")
      (node (ref "FB22") (pin "2") (pinfunction "P$2_2") (pintype "passive"))
      (node (ref "J2") (pin "5") (pinfunction "3.1_5") (pintype "bidirectional"))
      (node (ref "J2") (pin "6") (pinfunction "3.2_6") (pintype "bidirectional"))
    )
    (net (code "42") (name "IN4") (class "Default")
      (node (ref "FB21") (pin "2") (pinfunction "P$2_2") (pintype "passive"))
      (node (ref "J2") (pin "7") (pinfunction "4.1_7") (pintype "bidirectional"))
      (node (ref "J2") (pin "8") (pinfunction "4.2_8") (pintype "bidirectional"))
    )
    (net (code "43") (name "IN5") (class "Default")
      (node (ref "FB17") (pin "2") (pinfunction "P$2_2") (pintype "passive"))
      (node (ref "J2") (pin "10") (pinfunction "5.2_10") (pintype "bidirectional"))
      (node (ref "J2") (pin "9") (pinfunction "5.1_9") (pintype "bidirectional"))
    )
    (net (code "44") (name "IN6") (class "Default")
      (node (ref "FB18") (pin "2") (pinfunction "P$2_2") (pintype "passive"))
      (node (ref "J2") (pin "11") (pinfunction "6.1_11") (pintype "bidirectional"))
      (node (ref "J2") (pin "12") (pinfunction "6.2_12") (pintype "bidirectional"))
    )
    (net (code "45") (name "IN7") (class "Default")
      (node (ref "FB19") (pin "2") (pinfunction "P$2_2") (pintype "passive"))
      (node (ref "J2") (pin "13") (pinfunction "7.1_13") (pintype "bidirectional"))
      (node (ref "J2") (pin "14") (pinfunction "7.2_14") (pintype "bidirectional"))
    )
    (net (code "46") (name "IN8") (class "Default")
      (node (ref "FB20") (pin "2") (pinfunction "P$2_2") (pintype "passive"))
      (node (ref "J2") (pin "15") (pinfunction "8.1_15") (pintype "bidirectional"))
      (node (ref "J2") (pin "16") (pinfunction "8.2_16") (pintype "bidirectional"))
    )
    (net (code "47") (name "IO1") (class "Default")
      (node (ref "IC5") (pin "18") (pinfunction "PIO3_4/CT16B0_CAP1/RXD_18") (pintype "bidirectional"))
      (node (ref "R80") (pin "2") (pinfunction "2_2") (pintype "passive"))
    )
    (net (code "48") (name "IO2") (class "Default")
      (node (ref "IC5") (pin "14") (pinfunction "PIO0_3_14") (pintype "bidirectional"))
      (node (ref "R77") (pin "2") (pinfunction "2_2") (pintype "passive"))
    )
    (net (code "49") (name "IO3") (class "Default")
      (node (ref "IC5") (pin "20") (pinfunction "PIO2_5/CT32B0_MAT0_20") (pintype "bidirectional"))
      (node (ref "R78") (pin "2") (pinfunction "2_2") (pintype "passive"))
    )
    (net (code "50") (name "IO4") (class "Default")
      (node (ref "IC5") (pin "23") (pinfunction "PIO0_7/CTS_23") (pintype "bidirectional"))
      (node (ref "R79") (pin "2") (pinfunction "2_2") (pintype "passive"))
    )
    (net (code "51") (name "IO5") (class "Default")
      (node (ref "IC5") (pin "21") (pinfunction "PIO3_5/CT16B1_CAP1/TXD_21") (pintype "bidirectional"))
      (node (ref "R76") (pin "2") (pinfunction "2_2") (pintype "passive"))
    )
    (net (code "52") (name "IO6") (class "Default")
      (node (ref "IC5") (pin "13") (pinfunction "PIO2_1/DSR/SCK1_13") (pintype "bidirectional"))
      (node (ref "R73") (pin "2") (pinfunction "2_2") (pintype "passive"))
    )
    (net (code "53") (name "IO7") (class "Default")
      (node (ref "IC5") (pin "22") (pinfunction "PIO0_6/SCK0_22") (pintype "bidirectional"))
      (node (ref "R74") (pin "2") (pinfunction "2_2") (pintype "passive"))
    )
    (net (code "54") (name "IO8") (class "Default")
      (node (ref "IC5") (pin "24") (pinfunction "PIO2_9/CT32B0_CAP0_24") (pintype "bidirectional"))
      (node (ref "R75") (pin "2") (pinfunction "2_2") (pintype "passive"))
    )
    (net (code "55") (name "IO9") (class "Default")
      (node (ref "IC5") (pin "27") (pinfunction "PIO0_8/MISO0/CT16B0_MAT0_27") (pintype "bidirectional"))
      (node (ref "R12") (pin "2") (pinfunction "2_2") (pintype "passive"))
    )
    (net (code "56") (name "IO10") (class "Default")
      (node (ref "IC5") (pin "25") (pinfunction "PIO2_10_25") (pintype "bidirectional"))
      (node (ref "R9") (pin "2") (pinfunction "2_2") (pintype "passive"))
    )
    (net (code "57") (name "IO11") (class "Default")
      (node (ref "IC5") (pin "30") (pinfunction "PIO1_10/AD6/CT16B1_MAT1/MISO1_30") (pintype "bidirectional"))
      (node (ref "R10") (pin "2") (pinfunction "2_2") (pintype "passive"))
    )
    (net (code "58") (name "IO12") (class "Default")
      (node (ref "IC5") (pin "28") (pinfunction "PIO0_9/MOSI0/CT16B0_MAT1_28") (pintype "bidirectional"))
      (node (ref "R11") (pin "2") (pinfunction "2_2") (pintype "passive"))
    )
    (net (code "59") (name "IO13") (class "Default")
      (node (ref "IC5") (pin "40") (pinfunction "PIO1_4/AD5/CT32B1_MAT3/WAKEUP_40") (pintype "bidirectional"))
      (node (ref "R16") (pin "2") (pinfunction "2_2") (pintype "passive"))
    )
    (net (code "60") (name "IO14") (class "Default")
      (node (ref "IC5") (pin "10") (pinfunction "PIO0_2/SSEL0/CT16B0_CAP0_10") (pintype "bidirectional"))
      (node (ref "R13") (pin "2") (pinfunction "2_2") (pintype "passive"))
    )
    (net (code "61") (name "IO15") (class "Default")
      (node (ref "IC5") (pin "11") (pinfunction "PIO2_7/CT32B0_MAT2/RXD_11") (pintype "bidirectional"))
      (node (ref "R14") (pin "2") (pinfunction "2_2") (pintype "passive"))
    )
    (net (code "62") (name "IO16") (class "Default")
      (node (ref "IC5") (pin "12") (pinfunction "PIO2_8/CT32B0_MAT3/TXD_12") (pintype "bidirectional"))
      (node (ref "R15") (pin "2") (pinfunction "2_2") (pintype "passive"))
    )
    (net (code "63") (name "ISP_EN") (class "Default")
      (node (ref "IC5") (pin "4") (pinfunction "PIO0_1/CLKOUT/CT32B0_MAT2_4") (pintype "bidirectional"))
      (node (ref "R56") (pin "1") (pinfunction "1_1") (pintype "passive"))
      (node (ref "R69") (pin "1") (pinfunction "1_1") (pintype "passive"))
    )
    (net (code "64") (name "MISO1") (class "Default")
      (node (ref "IC5") (pin "26") (pinfunction "PIO2_2/DCD/MISO1_26") (pintype "bidirectional"))
      (node (ref "IC6") (pin "2") (pinfunction "SO_2") (pintype "bidirectional"))
      (node (ref "J1") (pin "4") (pinfunction "4_4") (pintype "passive"))
      (node (ref "JP1") (pin "4") (pinfunction "4_4") (pintype "passive"))
    )
    (net (code "65") (name "MOSI1") (class "Default")
      (node (ref "IC5") (pin "38") (pinfunction "PIO2_3/RI/MOSI1_38") (pintype "bidirectional"))
      (node (ref "IC6") (pin "5") (pinfunction "SI/SDA_5") (pintype "bidirectional"))
      (node (ref "J1") (pin "5") (pinfunction "5_5") (pintype "passive"))
      (node (ref "JP1") (pin "5") (pinfunction "5_5") (pintype "passive"))
    )
    (net (code "66") (name "Net-(D9-A1)") (class "Default")
      (node (ref "D3") (pin "C") (pinfunction "C_C") (pintype "passive"))
      (node (ref "D9") (pin "1") (pinfunction "A1_1") (pintype "passive"))
      (node (ref "R10") (pin "1") (pinfunction "1_1") (pintype "passive"))
      (node (ref "R3") (pin "2") (pinfunction "2_2") (pintype "passive"))
    )
    (net (code "67") (name "Net-(D9-A2)") (class "Default")
      (node (ref "D4") (pin "C") (pinfunction "C_C") (pintype "passive"))
      (node (ref "D9") (pin "2") (pinfunction "A2_2") (pintype "passive"))
      (node (ref "R11") (pin "1") (pinfunction "1_1") (pintype "passive"))
      (node (ref "R4") (pin "2") (pinfunction "2_2") (pintype "passive"))
    )
    (net (code "68") (name "Net-(D10-A1)") (class "Default")
      (node (ref "D10") (pin "1") (pinfunction "A1_1") (pintype "passive"))
      (node (ref "D2") (pin "C") (pinfunction "C_C") (pintype "passive"))
      (node (ref "R2") (pin "2") (pinfunction "2_2") (pintype "passive"))
      (node (ref "R9") (pin "1") (pinfunction "1_1") (pintype "passive"))
    )
    (net (code "69") (name "Net-(D10-A2)") (class "Default")
      (node (ref "D1") (pin "C") (pinfunction "C_C") (pintype "passive"))
      (node (ref "D10") (pin "2") (pinfunction "A2_2") (pintype "passive"))
      (node (ref "R1") (pin "2") (pinfunction "2_2") (pintype "passive"))
      (node (ref "R12") (pin "1") (pinfunction "1_1") (pintype "passive"))
    )
    (net (code "70") (name "Net-(D11-A1)") (class "Default")
      (node (ref "D11") (pin "1") (pinfunction "A1_1") (pintype "passive"))
      (node (ref "D5") (pin "C") (pinfunction "C_C") (pintype "passive"))
      (node (ref "R15") (pin "1") (pinfunction "1_1") (pintype "passive"))
      (node (ref "R8") (pin "2") (pinfunction "2_2") (pintype "passive"))
    )
    (net (code "71") (name "Net-(D11-A2)") (class "Default")
      (node (ref "D11") (pin "2") (pinfunction "A2_2") (pintype "passive"))
      (node (ref "D6") (pin "C") (pinfunction "C_C") (pintype "passive"))
      (node (ref "R14") (pin "1") (pinfunction "1_1") (pintype "passive"))
      (node (ref "R7") (pin "2") (pinfunction "2_2") (pintype "passive"))
    )
    (net (code "72") (name "Net-(D12-A1)") (class "Default")
      (node (ref "D12") (pin "1") (pinfunction "A1_1") (pintype "passive"))
      (node (ref "D8") (pin "C") (pinfunction "C_C") (pintype "passive"))
      (node (ref "R16") (pin "1") (pinfunction "1_1") (pintype "passive"))
      (node (ref "R5") (pin "2") (pinfunction "2_2") (pintype "passive"))
    )
    (net (code "73") (name "Net-(D12-A2)") (class "Default")
      (node (ref "D12") (pin "2") (pinfunction "A2_2") (pintype "passive"))
      (node (ref "D7") (pin "C") (pinfunction "C_C") (pintype "passive"))
      (node (ref "R13") (pin "1") (pinfunction "1_1") (pintype "passive"))
      (node (ref "R6") (pin "2") (pinfunction "2_2") (pintype "passive"))
    )
    (net (code "74") (name "Net-(FB1-P$1)") (class "Default")
      (node (ref "F1") (pin "1") (pinfunction "1_1") (pintype "passive"))
      (node (ref "FB1") (pin "1") (pinfunction "P$1_1") (pintype "passive"))
    )
    (net (code "75") (name "Net-(FB1-P$2)") (class "Default")
      (node (ref "FB1") (pin "2") (pinfunction "P$2_2") (pintype "passive"))
      (node (ref "X1") (pin "3") (pinfunction "S_3") (pintype "passive"))
    )
    (net (code "76") (name "Net-(FB2-P$1)") (class "Default")
      (node (ref "F2") (pin "1") (pinfunction "1_1") (pintype "passive"))
      (node (ref "FB2") (pin "1") (pinfunction "P$1_1") (pintype "passive"))
    )
    (net (code "77") (name "Net-(FB3-P$1)") (class "Default")
      (node (ref "F3") (pin "1") (pinfunction "1_1") (pintype "passive"))
      (node (ref "FB3") (pin "1") (pinfunction "P$1_1") (pintype "passive"))
    )
    (net (code "78") (name "Net-(FB3-P$2)") (class "Default")
      (node (ref "FB3") (pin "2") (pinfunction "P$2_2") (pintype "passive"))
      (node (ref "X1") (pin "5") (pinfunction "S_5") (pintype "passive"))
    )
    (net (code "79") (name "Net-(FB4-P$1)") (class "Default")
      (node (ref "F4") (pin "1") (pinfunction "1_1") (pintype "passive"))
      (node (ref "FB4") (pin "1") (pinfunction "P$1_1") (pintype "passive"))
    )
    (net (code "80") (name "Net-(FB4-P$2)") (class "Default")
      (node (ref "FB4") (pin "2") (pinfunction "P$2_2") (pintype "passive"))
      (node (ref "X1") (pin "6") (pinfunction "S_6") (pintype "passive"))
    )
    (net (code "81") (name "Net-(FB5-P$1)") (class "Default")
      (node (ref "FB5") (pin "1") (pinfunction "P$1_1") (pintype "passive"))
      (node (ref "X1") (pin "7") (pinfunction "S_7") (pintype "passive"))
    )
    (net (code "82") (name "Net-(FB5-P$2)") (class "Default")
      (node (ref "F5") (pin "1") (pinfunction "1_1") (pintype "passive"))
      (node (ref "FB5") (pin "2") (pinfunction "P$2_2") (pintype "passive"))
    )
    (net (code "83") (name "Net-(FB6-P$1)") (class "Default")
      (node (ref "FB6") (pin "1") (pinfunction "P$1_1") (pintype "passive"))
      (node (ref "X1") (pin "8") (pinfunction "S_8") (pintype "passive"))
    )
    (net (code "84") (name "Net-(FB6-P$2)") (class "Default")
      (node (ref "F6") (pin "1") (pinfunction "1_1") (pintype "passive"))
      (node (ref "FB6") (pin "2") (pinfunction "P$2_2") (pintype "passive"))
    )
    (net (code "85") (name "Net-(FB7-P$1)") (class "Default")
      (node (ref "FB7") (pin "1") (pinfunction "P$1_1") (pintype "passive"))
      (node (ref "X1") (pin "9") (pinfunction "S_9") (pintype "passive"))
    )
    (net (code "86") (name "Net-(FB7-P$2)") (class "Default")
      (node (ref "F7") (pin "1") (pinfunction "1_1") (pintype "passive"))
      (node (ref "FB7") (pin "2") (pinfunction "P$2_2") (pintype "passive"))
    )
    (net (code "87") (name "Net-(FB8-P$1)") (class "Default")
      (node (ref "FB8") (pin "1") (pinfunction "P$1_1") (pintype "passive"))
      (node (ref "X1") (pin "10") (pinfunction "S_10") (pintype "passive"))
    )
    (net (code "88") (name "Net-(FB8-P$2)") (class "Default")
      (node (ref "F8") (pin "1") (pinfunction "1_1") (pintype "passive"))
      (node (ref "FB8") (pin "2") (pinfunction "P$2_2") (pintype "passive"))
    )
    (net (code "89") (name "Net-(FB17-P$1)") (class "Default")
      (node (ref "F9") (pin "1") (pinfunction "1_1") (pintype "passive"))
      (node (ref "FB17") (pin "1") (pinfunction "P$1_1") (pintype "passive"))
    )
    (net (code "90") (name "Net-(FB18-P$1)") (class "Default")
      (node (ref "F10") (pin "1") (pinfunction "1_1") (pintype "passive"))
      (node (ref "FB18") (pin "1") (pinfunction "P$1_1") (pintype "passive"))
    )
    (net (code "91") (name "Net-(FB19-P$1)") (class "Default")
      (node (ref "F11") (pin "1") (pinfunction "1_1") (pintype "passive"))
      (node (ref "FB19") (pin "1") (pinfunction "P$1_1") (pintype "passive"))
    )
    (net (code "92") (name "Net-(FB20-P$1)") (class "Default")
      (node (ref "F12") (pin "1") (pinfunction "1_1") (pintype "passive"))
      (node (ref "FB20") (pin "1") (pinfunction "P$1_1") (pintype "passive"))
    )
    (net (code "93") (name "Net-(FB21-P$1)") (class "Default")
      (node (ref "F16") (pin "1") (pinfunction "1_1") (pintype "passive"))
      (node (ref "FB21") (pin "1") (pinfunction "P$1_1") (pintype "passive"))
    )
    (net (code "94") (name "Net-(FB22-P$1)") (class "Default")
      (node (ref "F15") (pin "1") (pinfunction "1_1") (pintype "passive"))
      (node (ref "FB22") (pin "1") (pinfunction "P$1_1") (pintype "passive"))
    )
    (net (code "95") (name "Net-(FB23-P$1)") (class "Default")
      (node (ref "F14") (pin "1") (pinfunction "1_1") (pintype "passive"))
      (node (ref "FB23") (pin "1") (pinfunction "P$1_1") (pintype "passive"))
    )
    (net (code "96") (name "Net-(FB24-P$1)") (class "Default")
      (node (ref "F13") (pin "1") (pinfunction "1_1") (pintype "passive"))
      (node (ref "FB24") (pin "1") (pinfunction "P$1_1") (pintype "passive"))
    )
    (net (code "97") (name "Net-(IC5-PIO1_5{slash}RTS{slash}CT32B0_CAP0)") (class "Default")
      (node (ref "IC5") (pin "45") (pinfunction "PIO1_5/RTS/CT32B0_CAP0_45") (pintype "bidirectional"))
      (node (ref "TP6") (pin "TP") (pinfunction "TP_TP") (pintype "input"))
    )
    (net (code "98") (name "Net-(IC5-PIO2_11{slash}SCK0{slash}CT32B0_CAP1)") (class "Default")
      (node (ref "IC5") (pin "31") (pinfunction "PIO2_11/SCK0/CT32B0_CAP1_31") (pintype "bidirectional"))
      (node (ref "TP1") (pin "TP") (pinfunction "TP_TP") (pintype "input"))
    )
    (net (code "99") (name "Net-(IC5-PIO3_3{slash}RI{slash}CT16B0_CAP0)") (class "Default")
      (node (ref "IC5") (pin "48") (pinfunction "PIO3_3/RI/CT16B0_CAP0_48") (pintype "bidirectional"))
      (node (ref "R81") (pin "1") (pinfunction "1_1") (pintype "passive"))
    )
    (net (code "100") (name "Net-(IC5-TDI{slash}PIO0_11{slash}AD0{slash}CT32B0_MAT3)") (class "Default")
      (node (ref "IC5") (pin "32") (pinfunction "TDI/PIO0_11/AD0/CT32B0_MAT3_32") (pintype "bidirectional"))
      (node (ref "TP2") (pin "TP") (pinfunction "TP_TP") (pintype "input"))
    )
    (net (code "101") (name "Net-(IC5-TDO{slash}PIO1_1{slash}AD2{slash}CT32B1_MAT0)") (class "Default")
      (node (ref "IC5") (pin "34") (pinfunction "TDO/PIO1_1/AD2/CT32B1_MAT0_34") (pintype "bidirectional"))
      (node (ref "TP4") (pin "TP") (pinfunction "TP_TP") (pintype "input"))
    )
    (net (code "102") (name "Net-(IC5-TMS{slash}PIO1_0{slash}AD1{slash}CT32B1_CAP0)") (class "Default")
      (node (ref "IC5") (pin "33") (pinfunction "TMS/PIO1_0/AD1/CT32B1_CAP0_33") (pintype "bidirectional"))
      (node (ref "TP3") (pin "TP") (pinfunction "TP_TP") (pintype "input"))
    )
    (net (code "103") (name "Net-(IC5-TRST{slash}PIO1_2{slash}AD3{slash}CT32B1_MAT1)") (class "Default")
      (node (ref "IC5") (pin "35") (pinfunction "TRST/PIO1_2/AD3/CT32B1_MAT1_35") (pintype "bidirectional"))
      (node (ref "TP5") (pin "TP") (pinfunction "TP_TP") (pintype "input"))
    )
    (net (code "104") (name "Net-(LED5-PadA)") (class "Default")
      (node (ref "LED5") (pin "A") (pinfunction "A_A") (pintype "passive"))
      (node (ref "R57") (pin "1") (pinfunction "1_1") (pintype "passive"))
    )
    (net (code "105") (name "Net-(LED6-PadC)") (class "Default")
      (node (ref "LED6") (pin "C") (pinfunction "C_C") (pintype "passive"))
      (node (ref "R81") (pin "2") (pinfunction "2_2") (pintype "passive"))
    )
    (net (code "106") (name "Net-(Q3-FO)") (class "Default")
      (node (ref "C30") (pin "2") (pinfunction "2_2") (pintype "passive"))
      (node (ref "Q3") (pin "3") (pinfunction "FO_3") (pintype "output"))
    )
    (net (code "107") (name "Net-(TVS1-IO1)") (class "Default")
      (node (ref "F4") (pin "2") (pinfunction "2_2") (pintype "passive"))
      (node (ref "R4") (pin "1") (pinfunction "1_1") (pintype "passive"))
      (node (ref "TVS1") (pin "1") (pinfunction "IO1_1") (pintype "bidirectional"))
    )
    (net (code "108") (name "Net-(TVS1-IO2)") (class "Default")
      (node (ref "F2") (pin "2") (pinfunction "2_2") (pintype "passive"))
      (node (ref "R2") (pin "1") (pinfunction "1_1") (pintype "passive"))
      (node (ref "TVS1") (pin "3") (pinfunction "IO2_3") (pintype "bidirectional"))
    )
    (net (code "109") (name "Net-(TVS1-IO3)") (class "Default")
      (node (ref "F1") (pin "2") (pinfunction "2_2") (pintype "passive"))
      (node (ref "R1") (pin "1") (pinfunction "1_1") (pintype "passive"))
      (node (ref "TVS1") (pin "4") (pinfunction "IO3_4") (pintype "bidirectional"))
    )
    (net (code "110") (name "Net-(TVS1-IO4)") (class "Default")
      (node (ref "F3") (pin "2") (pinfunction "2_2") (pintype "passive"))
      (node (ref "R3") (pin "1") (pinfunction "1_1") (pintype "passive"))
      (node (ref "TVS1") (pin "6") (pinfunction "IO4_6") (pintype "bidirectional"))
    )
    (net (code "111") (name "Net-(TVS1-VBUS)") (class "Default")
      (node (ref "C1") (pin "2") (pinfunction "2_2") (pintype "passive"))
      (node (ref "TVS1") (pin "5") (pinfunction "VBUS_5") (pintype "bidirectional"))
    )
    (net (code "112") (name "Net-(TVS2-VBUS)") (class "Default")
      (node (ref "C2") (pin "2") (pinfunction "2_2") (pintype "passive"))
      (node (ref "TVS2") (pin "5") (pinfunction "VBUS_5") (pintype "bidirectional"))
    )
    (net (code "113") (name "Net-(TVS6-VBUS)") (class "Default")
      (node (ref "C32") (pin "2") (pinfunction "2_2") (pintype "passive"))
      (node (ref "TVS6") (pin "5") (pinfunction "VBUS_5") (pintype "bidirectional"))
    )
    (net (code "114") (name "Net-(TVS9-VBUS)") (class "Default")
      (node (ref "C33") (pin "2") (pinfunction "2_2") (pintype "passive"))
      (node (ref "TVS9") (pin "5") (pinfunction "VBUS_5") (pintype "bidirectional"))
    )
    (net (code "115") (name "PROG") (class "Default")
      (node (ref "IC5") (pin "2") (pinfunction "PIO2_0/DTR/SSEL1_2") (pintype "bidirectional"))
      (node (ref "JP18") (pin "1") (pinfunction "1_1") (pintype "passive"))
      (node (ref "LED5") (pin "C") (pinfunction "C_C") (pintype "passive"))
    )
    (net (code "116") (name "RESET") (class "Default")
      (node (ref "C26") (pin "2") (pinfunction "2_2") (pintype "passive"))
      (node (ref "IC5") (pin "3") (pinfunction "RESET/PIO0_0_3") (pintype "bidirectional"))
      (node (ref "R55") (pin "1") (pinfunction "1_1") (pintype "passive"))
      (node (ref "R68") (pin "2") (pinfunction "2_2") (pintype "passive"))
    )
    (net (code "117") (name "SCK1") (class "Default")
      (node (ref "IC5") (pin "43") (pinfunction "PIO3_2/DCD/CT16B0_MAT2/SCK1_43") (pintype "bidirectional"))
      (node (ref "IC6") (pin "6") (pinfunction "SCK_6") (pintype "bidirectional"))
      (node (ref "J1") (pin "3") (pinfunction "3_3") (pintype "passive"))
      (node (ref "JP1") (pin "3") (pinfunction "3_3") (pintype "passive"))
    )
    (net (code "118") (name "SSEL1") (class "Default")
      (node (ref "IC5") (pin "19") (pinfunction "PIO2_4/CT16B1_MAT1/SSEL1_19") (pintype "bidirectional"))
      (node (ref "IC6") (pin "1") (pinfunction "CS_1") (pintype "bidirectional"))
      (node (ref "J1") (pin "6") (pinfunction "6_6") (pintype "passive"))
      (node (ref "JP1") (pin "6") (pinfunction "6_6") (pintype "passive"))
      (node (ref "R72") (pin "1") (pinfunction "1_1") (pintype "passive"))
    )
    (net (code "119") (name "SWCLK") (class "Default")
      (node (ref "IC5") (pin "29") (pinfunction "SWCLK/PIO0_10/SCK0/CT16B0_MAT2_29") (pintype "bidirectional"))
      (node (ref "R66") (pin "1") (pinfunction "1_1") (pintype "passive"))
    )
    (net (code "120") (name "SWDIO") (class "Default")
      (node (ref "IC5") (pin "39") (pinfunction "SWDIO/PIO1_3/AD4/CT32B1_MAT2_39") (pintype "bidirectional"))
      (node (ref "R67") (pin "1") (pinfunction "1_1") (pintype "passive"))
    )
    (net (code "121") (name "unconnected-(IC5-XTALOUT-Pad7)") (class "Default")
      (node (ref "IC5") (pin "7") (pinfunction "XTALOUT_7") (pintype "output"))
    )
    (net (code "122") (name "unconnected-(JP17-Pad6)") (class "Default")
      (node (ref "JP17") (pin "6") (pinfunction "6_6") (pintype "passive"))
    )
    (net (code "123") (name "unconnected-(JP17-Pad8)") (class "Default")
      (node (ref "JP17") (pin "8") (pinfunction "8_8") (pintype "passive"))
    )
    (net (code "124") (name "unconnected-(JP21-Pad1)") (class "Default")
      (node (ref "JP21") (pin "1") (pinfunction "1_1") (pintype "passive"))
    )
    (net (code "125") (name "unconnected-(JP21-Pad2)") (class "Default")
      (node (ref "JP21") (pin "2") (pinfunction "2_2") (pintype "passive"))
    )
  )
)
